# ESP32-DevBoard-Prototype.net
KiCad netlist of a schematic drawn in EAGLE
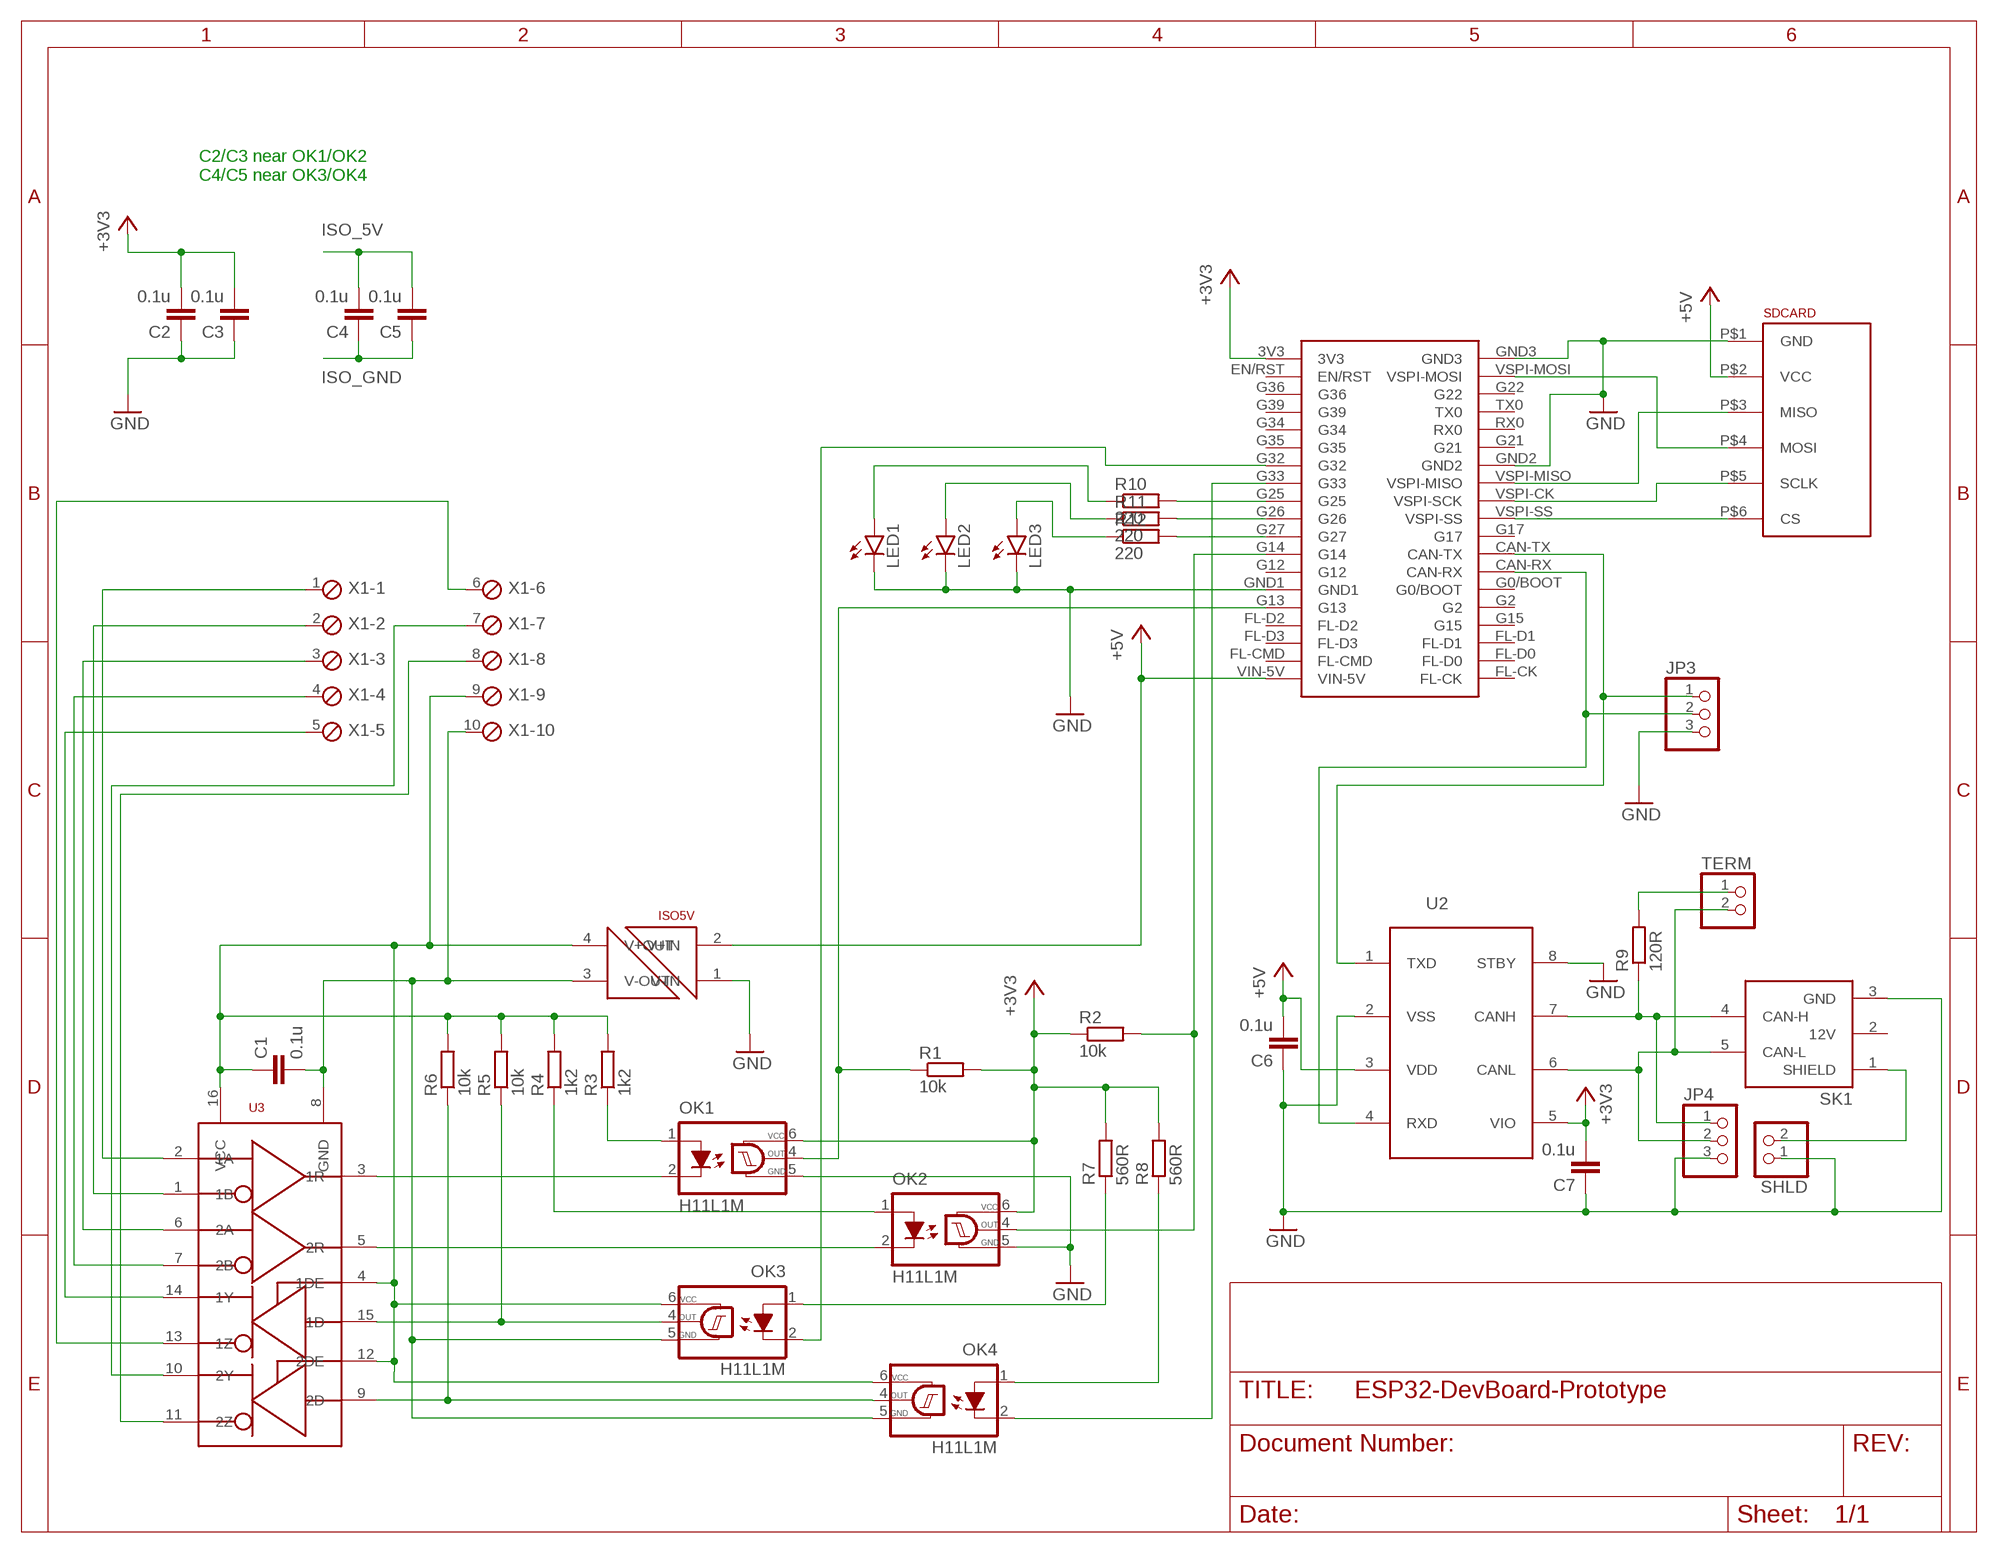
[diagram p0: schematic, sheet 1]

(export (version "E")
  (design (tool "Eeschema 10.0.6"))
  (components
    (comp (ref "C1")
      (value "0.1u")
      (footprint "eagle-import:C050-025X075")
      (libsource (lib "eagle-import") (part "C-EU050-025X075"))
    )
    (comp (ref "C2")
      (value "0.1u")
      (footprint "eagle-import:C050-025X075")
      (libsource (lib "eagle-import") (part "C-EU050-025X075"))
    )
    (comp (ref "C3")
      (value "0.1u")
      (footprint "eagle-import:C050-025X075")
      (libsource (lib "eagle-import") (part "C-EU050-025X075"))
    )
    (comp (ref "C4")
      (value "0.1u")
      (footprint "eagle-import:C050-025X075")
      (libsource (lib "eagle-import") (part "C-EU050-025X075"))
    )
    (comp (ref "C5")
      (value "0.1u")
      (footprint "eagle-import:C050-025X075")
      (libsource (lib "eagle-import") (part "C-EU050-025X075"))
    )
    (comp (ref "C6")
      (value "0.1u")
      (footprint "eagle-import:C050-025X075")
      (libsource (lib "eagle-import") (part "C-EU050-025X075"))
    )
    (comp (ref "C7")
      (value "0.1u")
      (footprint "eagle-import:C050-025X075")
      (libsource (lib "eagle-import") (part "C-EU050-025X075"))
    )
    (comp (ref "ISO5V")
      (value "RFM-0505S")
      (footprint "eagle-import:RFM-0505S")
      (libsource (lib "eagle-import") (part "RFM-0505S"))
    )
    (comp (ref "JP3")
      (value "PINHD-1X3")
      (footprint "eagle-import:1X03")
      (libsource (lib "eagle-import") (part "PINHD-1X3"))
    )
    (comp (ref "JP4")
      (value "PINHD-1X3")
      (footprint "eagle-import:1X03")
      (libsource (lib "eagle-import") (part "PINHD-1X3"))
    )
    (comp (ref "LED1")
      (value "LED5MM")
      (footprint "eagle-import:LED5MM")
      (libsource (lib "eagle-import") (part "LED5MM"))
    )
    (comp (ref "LED2")
      (value "LED5MM")
      (footprint "eagle-import:LED5MM")
      (libsource (lib "eagle-import") (part "LED5MM"))
    )
    (comp (ref "LED3")
      (value "LED5MM")
      (footprint "eagle-import:LED5MM")
      (libsource (lib "eagle-import") (part "LED5MM"))
    )
    (comp (ref "OK1")
      (value "H11L1M")
      (footprint "eagle-import:DIL06")
      (fields (field (name "MF") "FAIRCHILD SEMICONDUCTOR") (field (name "MPN") "H11L1-M"))
      (libsource (lib "eagle-import") (part "H11LM1"))
    )
    (comp (ref "OK2")
      (value "H11L1M")
      (footprint "eagle-import:DIL06")
      (fields (field (name "MF") "FAIRCHILD SEMICONDUCTOR") (field (name "MPN") "H11L1-M"))
      (libsource (lib "eagle-import") (part "H11LM1"))
    )
    (comp (ref "OK3")
      (value "H11L1M")
      (footprint "eagle-import:DIL06")
      (fields (field (name "MF") "FAIRCHILD SEMICONDUCTOR") (field (name "MPN") "H11L1-M"))
      (libsource (lib "eagle-import") (part "H11LM1"))
    )
    (comp (ref "OK4")
      (value "H11L1M")
      (footprint "eagle-import:DIL06")
      (fields (field (name "MF") "FAIRCHILD SEMICONDUCTOR") (field (name "MPN") "H11L1-M"))
      (libsource (lib "eagle-import") (part "H11LM1"))
    )
    (comp (ref "R1")
      (value "10k")
      (footprint "eagle-import:0207_10")
      (libsource (lib "eagle-import") (part "R-EU_0207/10"))
    )
    (comp (ref "R2")
      (value "10k")
      (footprint "eagle-import:0207_10")
      (libsource (lib "eagle-import") (part "R-EU_0207/10"))
    )
    (comp (ref "R3")
      (value "1k2")
      (footprint "eagle-import:0207_10")
      (libsource (lib "eagle-import") (part "R-EU_0207/10"))
    )
    (comp (ref "R4")
      (value "1k2")
      (footprint "eagle-import:0207_10")
      (libsource (lib "eagle-import") (part "R-EU_0207/10"))
    )
    (comp (ref "R5")
      (value "10k")
      (footprint "eagle-import:0207_10")
      (libsource (lib "eagle-import") (part "R-EU_0207/10"))
    )
    (comp (ref "R6")
      (value "10k")
      (footprint "eagle-import:0207_10")
      (libsource (lib "eagle-import") (part "R-EU_0207/10"))
    )
    (comp (ref "R7")
      (value "560R")
      (footprint "eagle-import:0207_10")
      (libsource (lib "eagle-import") (part "R-EU_0207/10"))
    )
    (comp (ref "R8")
      (value "560R")
      (footprint "eagle-import:0207_10")
      (libsource (lib "eagle-import") (part "R-EU_0207/10"))
    )
    (comp (ref "R9")
      (value "120R")
      (footprint "eagle-import:0207_10")
      (libsource (lib "eagle-import") (part "R-EU_0207/10"))
    )
    (comp (ref "R10")
      (value "220")
      (footprint "eagle-import:0207_10")
      (libsource (lib "eagle-import") (part "R-EU_0207/10"))
    )
    (comp (ref "R11")
      (value "220")
      (footprint "eagle-import:0207_10")
      (libsource (lib "eagle-import") (part "R-EU_0207/10"))
    )
    (comp (ref "R12")
      (value "220")
      (footprint "eagle-import:0207_10")
      (libsource (lib "eagle-import") (part "R-EU_0207/10"))
    )
    (comp (ref "SDCARD")
      (value "MICROSD-BREAKOUT")
      (footprint "eagle-import:MICROSD-BREAKOUT")
      (libsource (lib "eagle-import") (part "MICROSD-BREAKOUT"))
    )
    (comp (ref "SHLD")
      (value "PINHD-1X2")
      (footprint "eagle-import:1X02")
      (libsource (lib "eagle-import") (part "PINHD-1X2"))
    )
    (comp (ref "SK1")
      (value "NMEA2000-TOPSIDE")
      (footprint "eagle-import:NMEA2000-TOPSIDE")
      (libsource (lib "eagle-import") (part "NMEA2000-TOPSIDE"))
    )
    (comp (ref "TERM")
      (value "PINHD-1X2")
      (footprint "eagle-import:1X02")
      (libsource (lib "eagle-import") (part "PINHD-1X2"))
    )
    (comp (ref "U1")
      (value "ESP32-DEVBOARD")
      (footprint "eagle-import:ESP32-DEVBOARD")
      (libsource (lib "eagle-import") (part "ESP32-DEVBOARD"))
    )
    (comp (ref "U2")
      (value "MCP2562-TH")
      (footprint "eagle-import:DIP8")
      (libsource (lib "eagle-import") (part "MCP2562-TH"))
    )
    (comp (ref "U3")
      (value "SN65C1168")
      (footprint "eagle-import:DIP16")
      (libsource (lib "eagle-import") (part "SN65C1168"))
    )
    (comp (ref "X1")
      (value "MPT10")
      (footprint "eagle-import:10POL254")
      (libsource (lib "eagle-import") (part "MPT10"))
    )
  )
  (nets
    (net (code "1") (name "+3V3") (class "Default")
      (node (ref "C2") (pin "2") (pinfunction "2_2") (pintype "passive"))
      (node (ref "C3") (pin "2") (pinfunction "2_2") (pintype "passive"))
      (node (ref "C7") (pin "2") (pinfunction "2_2") (pintype "passive"))
      (node (ref "OK1") (pin "6") (pinfunction "VCC_6") (pintype "power_in"))
      (node (ref "OK2") (pin "6") (pinfunction "VCC_6") (pintype "power_in"))
      (node (ref "R1") (pin "2") (pinfunction "2_2") (pintype "passive"))
      (node (ref "R2") (pin "1") (pinfunction "1_1") (pintype "passive"))
      (node (ref "R7") (pin "2") (pinfunction "2_2") (pintype "passive"))
      (node (ref "R8") (pin "2") (pinfunction "2_2") (pintype "passive"))
      (node (ref "U1") (pin "3V3") (pinfunction "3V3_3V3") (pintype "bidirectional"))
      (node (ref "U2") (pin "5") (pinfunction "VIO_5") (pintype "bidirectional"))
    )
    (net (code "2") (name "+5V") (class "Default")
      (node (ref "C6") (pin "2") (pinfunction "2_2") (pintype "passive"))
      (node (ref "ISO5V") (pin "2") (pinfunction "V+IN_2") (pintype "bidirectional"))
      (node (ref "SDCARD") (pin "P$2") (pinfunction "VCC_P$2") (pintype "bidirectional"))
      (node (ref "U1") (pin "VIN-5V") (pinfunction "VIN-5V_VIN-5V") (pintype "bidirectional"))
      (node (ref "U2") (pin "3") (pinfunction "VDD_3") (pintype "bidirectional"))
    )
    (net (code "3") (name "/ISO_5V") (class "Default")
      (node (ref "C1") (pin "1") (pinfunction "1_1") (pintype "passive"))
      (node (ref "C4") (pin "2") (pinfunction "2_2") (pintype "passive"))
      (node (ref "C5") (pin "2") (pinfunction "2_2") (pintype "passive"))
      (node (ref "ISO5V") (pin "4") (pinfunction "V+OUT_4") (pintype "bidirectional"))
      (node (ref "OK3") (pin "6") (pinfunction "VCC_6") (pintype "power_in"))
      (node (ref "OK4") (pin "6") (pinfunction "VCC_6") (pintype "power_in"))
      (node (ref "R3") (pin "2") (pinfunction "2_2") (pintype "passive"))
      (node (ref "R4") (pin "2") (pinfunction "2_2") (pintype "passive"))
      (node (ref "R5") (pin "2") (pinfunction "2_2") (pintype "passive"))
      (node (ref "R6") (pin "2") (pinfunction "2_2") (pintype "passive"))
      (node (ref "U3") (pin "12") (pinfunction "2DE_12") (pintype "bidirectional"))
      (node (ref "U3") (pin "16") (pinfunction "VCC_16") (pintype "bidirectional"))
      (node (ref "U3") (pin "4") (pinfunction "1DE_4") (pintype "bidirectional"))
      (node (ref "X1") (pin "9") (pinfunction "1_9") (pintype "passive"))
    )
    (net (code "4") (name "/ISO_GND") (class "Default")
      (node (ref "C1") (pin "2") (pinfunction "2_2") (pintype "passive"))
      (node (ref "C4") (pin "1") (pinfunction "1_1") (pintype "passive"))
      (node (ref "C5") (pin "1") (pinfunction "1_1") (pintype "passive"))
      (node (ref "ISO5V") (pin "3") (pinfunction "V-OUT_3") (pintype "bidirectional"))
      (node (ref "OK3") (pin "5") (pinfunction "GND_5") (pintype "power_in"))
      (node (ref "OK4") (pin "5") (pinfunction "GND_5") (pintype "power_in"))
      (node (ref "U3") (pin "8") (pinfunction "GND_8") (pintype "bidirectional"))
      (node (ref "X1") (pin "10") (pinfunction "1_10") (pintype "passive"))
    )
    (net (code "5") (name "GND") (class "Default")
      (node (ref "C2") (pin "1") (pinfunction "1_1") (pintype "passive"))
      (node (ref "C3") (pin "1") (pinfunction "1_1") (pintype "passive"))
      (node (ref "C6") (pin "1") (pinfunction "1_1") (pintype "passive"))
      (node (ref "C7") (pin "1") (pinfunction "1_1") (pintype "passive"))
      (node (ref "ISO5V") (pin "1") (pinfunction "V-IN_1") (pintype "bidirectional"))
      (node (ref "JP3") (pin "3") (pinfunction "3_3") (pintype "passive"))
      (node (ref "JP4") (pin "3") (pinfunction "3_3") (pintype "passive"))
      (node (ref "LED1") (pin "K") (pinfunction "C_K") (pintype "passive"))
      (node (ref "LED2") (pin "K") (pinfunction "C_K") (pintype "passive"))
      (node (ref "LED3") (pin "K") (pinfunction "C_K") (pintype "passive"))
      (node (ref "OK1") (pin "5") (pinfunction "GND_5") (pintype "power_in"))
      (node (ref "OK2") (pin "5") (pinfunction "GND_5") (pintype "power_in"))
      (node (ref "SDCARD") (pin "P$1") (pinfunction "GND_P$1") (pintype "bidirectional"))
      (node (ref "SHLD") (pin "1") (pinfunction "1_1") (pintype "passive"))
      (node (ref "SK1") (pin "3") (pinfunction "GND_3") (pintype "bidirectional"))
      (node (ref "U1") (pin "GND1") (pinfunction "GND1_GND1") (pintype "bidirectional"))
      (node (ref "U1") (pin "GND2") (pinfunction "GND2_GND2") (pintype "bidirectional"))
      (node (ref "U1") (pin "GND3") (pinfunction "GND3_GND3") (pintype "bidirectional"))
      (node (ref "U2") (pin "2") (pinfunction "VSS_2") (pintype "bidirectional"))
      (node (ref "U2") (pin "8") (pinfunction "STBY_8") (pintype "bidirectional"))
    )
    (net (code "6") (name "Net-(LED1-PadA)") (class "Default")
      (node (ref "LED1") (pin "A") (pinfunction "A_A") (pintype "passive"))
      (node (ref "R10") (pin "1") (pinfunction "1_1") (pintype "passive"))
    )
    (net (code "7") (name "Net-(LED2-PadA)") (class "Default")
      (node (ref "LED2") (pin "A") (pinfunction "A_A") (pintype "passive"))
      (node (ref "R11") (pin "1") (pinfunction "1_1") (pintype "passive"))
    )
    (net (code "8") (name "Net-(LED3-PadA)") (class "Default")
      (node (ref "LED3") (pin "A") (pinfunction "A_A") (pintype "passive"))
      (node (ref "R12") (pin "1") (pinfunction "1_1") (pintype "passive"))
    )
    (net (code "9") (name "Net-(OK1-A)") (class "Default")
      (node (ref "OK1") (pin "1") (pinfunction "A_1") (pintype "passive"))
      (node (ref "R3") (pin "1") (pinfunction "1_1") (pintype "passive"))
    )
    (net (code "10") (name "Net-(OK1-C)") (class "Default")
      (node (ref "OK1") (pin "2") (pinfunction "C_2") (pintype "passive"))
      (node (ref "U3") (pin "3") (pinfunction "1R_3") (pintype "bidirectional"))
    )
    (net (code "11") (name "Net-(OK1-OUT)") (class "Default")
      (node (ref "OK1") (pin "4") (pinfunction "OUT_4") (pintype "output"))
      (node (ref "R1") (pin "1") (pinfunction "1_1") (pintype "passive"))
      (node (ref "U1") (pin "G13") (pinfunction "G13_G13") (pintype "bidirectional"))
    )
    (net (code "12") (name "Net-(OK2-A)") (class "Default")
      (node (ref "OK2") (pin "1") (pinfunction "A_1") (pintype "passive"))
      (node (ref "R4") (pin "1") (pinfunction "1_1") (pintype "passive"))
    )
    (net (code "13") (name "Net-(OK2-C)") (class "Default")
      (node (ref "OK2") (pin "2") (pinfunction "C_2") (pintype "passive"))
      (node (ref "U3") (pin "5") (pinfunction "2R_5") (pintype "bidirectional"))
    )
    (net (code "14") (name "Net-(OK2-OUT)") (class "Default")
      (node (ref "OK2") (pin "4") (pinfunction "OUT_4") (pintype "output"))
      (node (ref "R2") (pin "2") (pinfunction "2_2") (pintype "passive"))
      (node (ref "U1") (pin "G14") (pinfunction "G14_G14") (pintype "bidirectional"))
    )
    (net (code "15") (name "Net-(OK3-A)") (class "Default")
      (node (ref "OK3") (pin "1") (pinfunction "A_1") (pintype "passive"))
      (node (ref "R7") (pin "1") (pinfunction "1_1") (pintype "passive"))
    )
    (net (code "16") (name "Net-(OK3-C)") (class "Default")
      (node (ref "OK3") (pin "2") (pinfunction "C_2") (pintype "passive"))
      (node (ref "U1") (pin "G32") (pinfunction "G32_G32") (pintype "bidirectional"))
    )
    (net (code "17") (name "Net-(OK3-OUT)") (class "Default")
      (node (ref "OK3") (pin "4") (pinfunction "OUT_4") (pintype "output"))
      (node (ref "R5") (pin "1") (pinfunction "1_1") (pintype "passive"))
      (node (ref "U3") (pin "15") (pinfunction "1D_15") (pintype "bidirectional"))
    )
    (net (code "18") (name "Net-(OK4-A)") (class "Default")
      (node (ref "OK4") (pin "1") (pinfunction "A_1") (pintype "passive"))
      (node (ref "R8") (pin "1") (pinfunction "1_1") (pintype "passive"))
    )
    (net (code "19") (name "Net-(OK4-C)") (class "Default")
      (node (ref "OK4") (pin "2") (pinfunction "C_2") (pintype "passive"))
      (node (ref "U1") (pin "G33") (pinfunction "G33_G33") (pintype "bidirectional"))
    )
    (net (code "20") (name "Net-(OK4-OUT)") (class "Default")
      (node (ref "OK4") (pin "4") (pinfunction "OUT_4") (pintype "output"))
      (node (ref "R6") (pin "1") (pinfunction "1_1") (pintype "passive"))
      (node (ref "U3") (pin "9") (pinfunction "2D_9") (pintype "bidirectional"))
    )
    (net (code "21") (name "Net-(R9-Pad2)") (class "Default")
      (node (ref "R9") (pin "2") (pinfunction "2_2") (pintype "passive"))
      (node (ref "TERM") (pin "1") (pinfunction "1_1") (pintype "passive"))
    )
    (net (code "22") (name "Net-(R10-Pad2)") (class "Default")
      (node (ref "R10") (pin "2") (pinfunction "2_2") (pintype "passive"))
      (node (ref "U1") (pin "G25") (pinfunction "G25_G25") (pintype "bidirectional"))
    )
    (net (code "23") (name "Net-(R11-Pad2)") (class "Default")
      (node (ref "R11") (pin "2") (pinfunction "2_2") (pintype "passive"))
      (node (ref "U1") (pin "G26") (pinfunction "G26_G26") (pintype "bidirectional"))
    )
    (net (code "24") (name "Net-(R12-Pad2)") (class "Default")
      (node (ref "R12") (pin "2") (pinfunction "2_2") (pintype "passive"))
      (node (ref "U1") (pin "G27") (pinfunction "G27_G27") (pintype "bidirectional"))
    )
    (net (code "25") (name "Net-(SDCARD-CS)") (class "Default")
      (node (ref "SDCARD") (pin "P$6") (pinfunction "CS_P$6") (pintype "bidirectional"))
      (node (ref "U1") (pin "VSPI-SS") (pinfunction "VSPI-SS_VSPI-SS") (pintype "bidirectional"))
    )
    (net (code "26") (name "Net-(SDCARD-MISO)") (class "Default")
      (node (ref "SDCARD") (pin "P$3") (pinfunction "MISO_P$3") (pintype "bidirectional"))
      (node (ref "U1") (pin "VSPI-MISO") (pinfunction "VSPI-MISO_VSPI-MISO") (pintype "bidirectional"))
    )
    (net (code "27") (name "Net-(SDCARD-MOSI)") (class "Default")
      (node (ref "SDCARD") (pin "P$4") (pinfunction "MOSI_P$4") (pintype "bidirectional"))
      (node (ref "U1") (pin "VSPI-MOSI") (pinfunction "VSPI-MOSI_VSPI-MOSI") (pintype "bidirectional"))
    )
    (net (code "28") (name "Net-(SDCARD-SCLK)") (class "Default")
      (node (ref "SDCARD") (pin "P$5") (pinfunction "SCLK_P$5") (pintype "bidirectional"))
      (node (ref "U1") (pin "VSPI-CK") (pinfunction "VSPI-SCK_VSPI-CK") (pintype "bidirectional"))
    )
    (net (code "29") (name "Net-(SK1-CAN-H)") (class "Default")
      (node (ref "JP4") (pin "1") (pinfunction "1_1") (pintype "passive"))
      (node (ref "R9") (pin "1") (pinfunction "1_1") (pintype "passive"))
      (node (ref "SK1") (pin "4") (pinfunction "CAN-H_4") (pintype "bidirectional"))
      (node (ref "U2") (pin "7") (pinfunction "CANH_7") (pintype "bidirectional"))
    )
    (net (code "30") (name "Net-(SK1-CAN-L)") (class "Default")
      (node (ref "JP4") (pin "2") (pinfunction "2_2") (pintype "passive"))
      (node (ref "SK1") (pin "5") (pinfunction "CAN-L_5") (pintype "bidirectional"))
      (node (ref "TERM") (pin "2") (pinfunction "2_2") (pintype "passive"))
      (node (ref "U2") (pin "6") (pinfunction "CANL_6") (pintype "bidirectional"))
    )
    (net (code "31") (name "Net-(SK1-SHIELD)") (class "Default")
      (node (ref "SHLD") (pin "2") (pinfunction "2_2") (pintype "passive"))
      (node (ref "SK1") (pin "1") (pinfunction "SHIELD_1") (pintype "bidirectional"))
    )
    (net (code "32") (name "Net-(U2-RXD)") (class "Default")
      (node (ref "JP3") (pin "2") (pinfunction "2_2") (pintype "passive"))
      (node (ref "U1") (pin "CAN-RX") (pinfunction "CAN-RX_CAN-RX") (pintype "bidirectional"))
      (node (ref "U2") (pin "4") (pinfunction "RXD_4") (pintype "bidirectional"))
    )
    (net (code "33") (name "Net-(U2-TXD)") (class "Default")
      (node (ref "JP3") (pin "1") (pinfunction "1_1") (pintype "passive"))
      (node (ref "U1") (pin "CAN-TX") (pinfunction "CAN-TX_CAN-TX") (pintype "bidirectional"))
      (node (ref "U2") (pin "1") (pinfunction "TXD_1") (pintype "bidirectional"))
    )
    (net (code "34") (name "Net-(U3-1A)") (class "Default")
      (node (ref "U3") (pin "2") (pinfunction "1A_2") (pintype "bidirectional"))
      (node (ref "X1") (pin "1") (pinfunction "1_1") (pintype "passive"))
    )
    (net (code "35") (name "Net-(U3-1B)") (class "Default")
      (node (ref "U3") (pin "1") (pinfunction "1B_1") (pintype "bidirectional"))
      (node (ref "X1") (pin "2") (pinfunction "1_2") (pintype "passive"))
    )
    (net (code "36") (name "Net-(U3-1Y)") (class "Default")
      (node (ref "U3") (pin "14") (pinfunction "1Y_14") (pintype "bidirectional"))
      (node (ref "X1") (pin "5") (pinfunction "1_5") (pintype "passive"))
    )
    (net (code "37") (name "Net-(U3-1Z)") (class "Default")
      (node (ref "U3") (pin "13") (pinfunction "1Z_13") (pintype "bidirectional"))
      (node (ref "X1") (pin "6") (pinfunction "1_6") (pintype "passive"))
    )
    (net (code "38") (name "Net-(U3-2A)") (class "Default")
      (node (ref "U3") (pin "6") (pinfunction "2A_6") (pintype "bidirectional"))
      (node (ref "X1") (pin "3") (pinfunction "1_3") (pintype "passive"))
    )
    (net (code "39") (name "Net-(U3-2B)") (class "Default")
      (node (ref "U3") (pin "7") (pinfunction "2B_7") (pintype "bidirectional"))
      (node (ref "X1") (pin "4") (pinfunction "1_4") (pintype "passive"))
    )
    (net (code "40") (name "Net-(U3-2Y)") (class "Default")
      (node (ref "U3") (pin "10") (pinfunction "2Y_10") (pintype "bidirectional"))
      (node (ref "X1") (pin "7") (pinfunction "1_7") (pintype "passive"))
    )
    (net (code "41") (name "Net-(U3-2Z)") (class "Default")
      (node (ref "U3") (pin "11") (pinfunction "2Z_11") (pintype "bidirectional"))
      (node (ref "X1") (pin "8") (pinfunction "1_8") (pintype "passive"))
    )
    (net (code "42") (name "unconnected-(SK1-12V-Pad2)") (class "Default")
      (node (ref "SK1") (pin "2") (pinfunction "12V_2") (pintype "bidirectional"))
    )
    (net (code "43") (name "unconnected-(U1-PadEN{slash}RST)") (class "Default")
      (node (ref "U1") (pin "EN/RST") (pinfunction "EN/RST_EN/RST") (pintype "bidirectional"))
    )
    (net (code "44") (name "unconnected-(U1-PadFL-CK)") (class "Default")
      (node (ref "U1") (pin "FL-CK") (pinfunction "FL-CK_FL-CK") (pintype "bidirectional"))
    )
    (net (code "45") (name "unconnected-(U1-PadFL-CMD)") (class "Default")
      (node (ref "U1") (pin "FL-CMD") (pinfunction "FL-CMD_FL-CMD") (pintype "bidirectional"))
    )
    (net (code "46") (name "unconnected-(U1-PadFL-D0)") (class "Default")
      (node (ref "U1") (pin "FL-D0") (pinfunction "FL-D0_FL-D0") (pintype "bidirectional"))
    )
    (net (code "47") (name "unconnected-(U1-PadFL-D1)") (class "Default")
      (node (ref "U1") (pin "FL-D1") (pinfunction "FL-D1_FL-D1") (pintype "bidirectional"))
    )
    (net (code "48") (name "unconnected-(U1-PadFL-D2)") (class "Default")
      (node (ref "U1") (pin "FL-D2") (pinfunction "FL-D2_FL-D2") (pintype "bidirectional"))
    )
    (net (code "49") (name "unconnected-(U1-PadFL-D3)") (class "Default")
      (node (ref "U1") (pin "FL-D3") (pinfunction "FL-D3_FL-D3") (pintype "bidirectional"))
    )
    (net (code "50") (name "unconnected-(U1-PadG0{slash}BOOT)") (class "Default")
      (node (ref "U1") (pin "G0/BOOT") (pinfunction "G0/BOOT_G0/BOOT") (pintype "bidirectional"))
    )
    (net (code "51") (name "unconnected-(U1-PadG2)") (class "Default")
      (node (ref "U1") (pin "G2") (pinfunction "G2_G2") (pintype "bidirectional"))
    )
    (net (code "52") (name "unconnected-(U1-PadG12)") (class "Default")
      (node (ref "U1") (pin "G12") (pinfunction "G12_G12") (pintype "bidirectional"))
    )
    (net (code "53") (name "unconnected-(U1-PadG15)") (class "Default")
      (node (ref "U1") (pin "G15") (pinfunction "G15_G15") (pintype "bidirectional"))
    )
    (net (code "54") (name "unconnected-(U1-PadG17)") (class "Default")
      (node (ref "U1") (pin "G17") (pinfunction "G17_G17") (pintype "bidirectional"))
    )
    (net (code "55") (name "unconnected-(U1-PadG21)") (class "Default")
      (node (ref "U1") (pin "G21") (pinfunction "G21_G21") (pintype "bidirectional"))
    )
    (net (code "56") (name "unconnected-(U1-PadG22)") (class "Default")
      (node (ref "U1") (pin "G22") (pinfunction "G22_G22") (pintype "bidirectional"))
    )
    (net (code "57") (name "unconnected-(U1-PadG34)") (class "Default")
      (node (ref "U1") (pin "G34") (pinfunction "G34_G34") (pintype "bidirectional"))
    )
    (net (code "58") (name "unconnected-(U1-PadG35)") (class "Default")
      (node (ref "U1") (pin "G35") (pinfunction "G35_G35") (pintype "bidirectional"))
    )
    (net (code "59") (name "unconnected-(U1-PadG36)") (class "Default")
      (node (ref "U1") (pin "G36") (pinfunction "G36_G36") (pintype "bidirectional"))
    )
    (net (code "60") (name "unconnected-(U1-PadG39)") (class "Default")
      (node (ref "U1") (pin "G39") (pinfunction "G39_G39") (pintype "bidirectional"))
    )
    (net (code "61") (name "unconnected-(U1-PadRX0)") (class "Default")
      (node (ref "U1") (pin "RX0") (pinfunction "RX0_RX0") (pintype "bidirectional"))
    )
    (net (code "62") (name "unconnected-(U1-PadTX0)") (class "Default")
      (node (ref "U1") (pin "TX0") (pinfunction "TX0_TX0") (pintype "bidirectional"))
    )
  )
)
